# GPS.net
KiCad netlist of a schematic drawn in Altium Designer
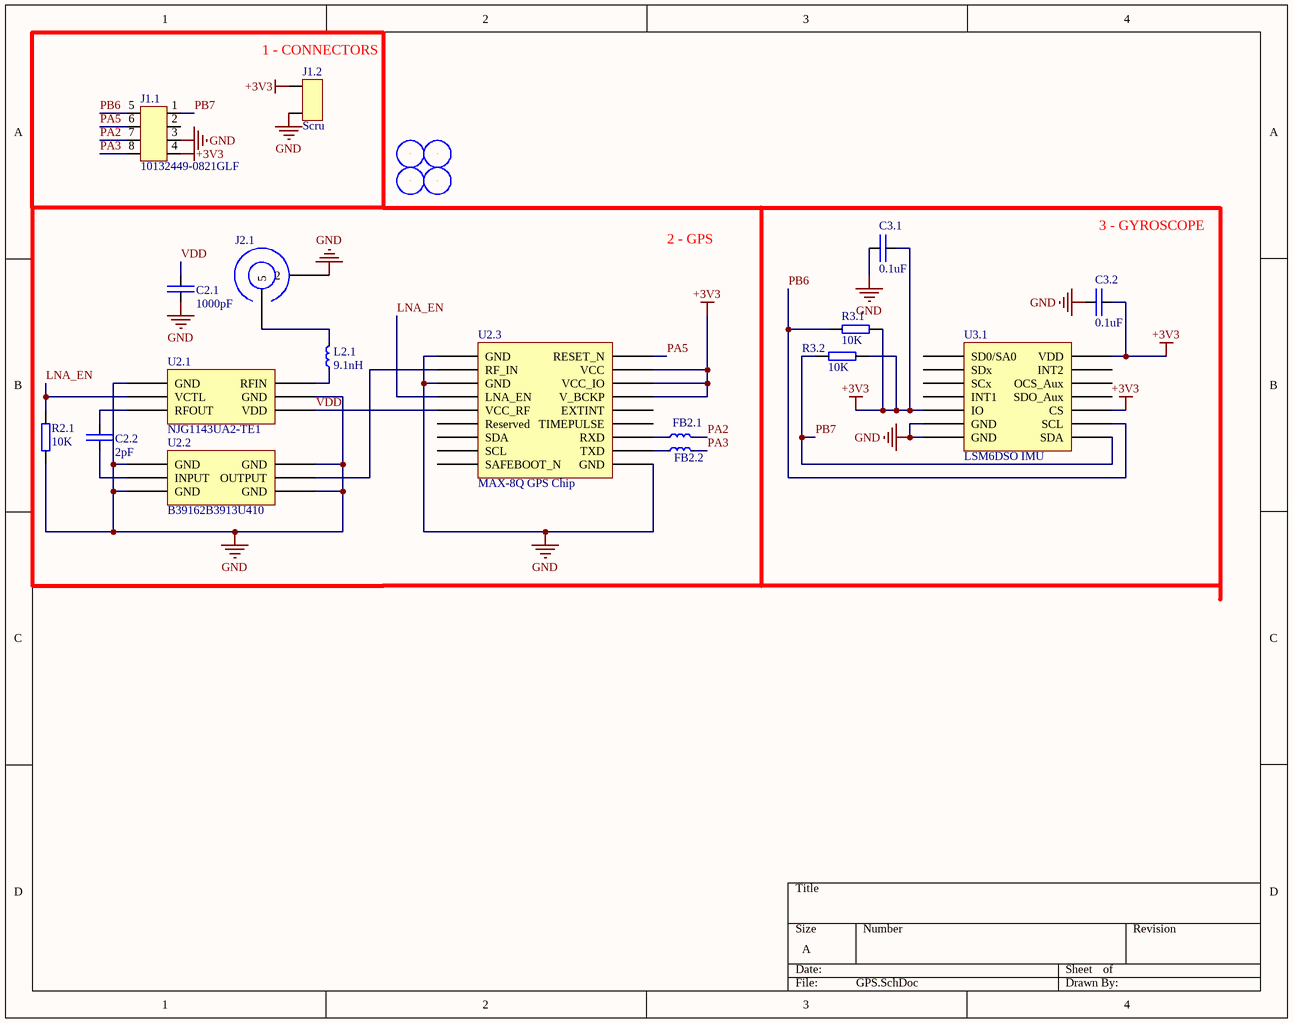
[diagram p0: GPS.SchDoc]

(export (version "E")
  (design (tool "Eeschema 10.0.6"))
  (components
    (comp (ref "C2.1")
      (value "1000pF")
      (footprint "0805")
      (description "1000pF ±5% 25V Ceramic Capacitor C0G, NP0 0805 (2012 Metric)")
      (libsource (lib "GPS_SchLib") (part "885012007040"))
    )
    (comp (ref "C2.2")
      (value "2pF")
      (footprint "0805")
      (description "2pF ±0.25pF 50V Ceramic Capacitor C0G, NP0 0805 (2012 Metric)")
      (libsource (lib "GPS_SchLib") (part "08055A2R0CAT2A"))
    )
    (comp (ref "C3.1")
      (value "0.1uF")
      (footprint "C0805")
      (description "CAP CER 0.1UF 50V X7R 0805")
      (fields
        (field (name "MANUFACTURER") "Samsung")
        (field (name "MANUFACTURER PART NUMBER") "CL21B104KBCWPNC")
      )
      (libsource (lib "Capacitors") (part "CL21B104KBCWPNC"))
    )
    (comp (ref "C3.2")
      (value "0.1uF")
      (footprint "C0805")
      (description "CAP CER 0.1UF 50V X7R 0805")
      (fields
        (field (name "MANUFACTURER") "Samsung")
        (field (name "MANUFACTURER PART NUMBER") "CL21B104KBCWPNC")
      )
      (libsource (lib "Capacitors") (part "CL21B104KBCWPNC"))
    )
    (comp (ref "FB2.1")
      (value "BLM15HD102SN1D")
      (footprint "L0402")
      (description "Ferrite Beads 0402 1Kohms Tape GHz Hi Spd Sig Line")
      (fields
        (field (name "MANUFACTURER") "Taiyo Yuden")
        (field (name "MANUFACTURER PART NUMBER") "NR6028T330M")
      )
      (libsource (lib "GPS_SchLib") (part "BLM15HD102SN1D"))
    )
    (comp (ref "FB2.2")
      (value "BLM15HD102SN1D")
      (footprint "L0402")
      (description "Ferrite Beads 0402 1Kohms Tape GHz Hi Spd Sig Line")
      (fields
        (field (name "MANUFACTURER") "Taiyo Yuden")
        (field (name "MANUFACTURER PART NUMBER") "NR6028T330M")
      )
      (libsource (lib "GPS_SchLib") (part "BLM15HD102SN1D"))
    )
    (comp (ref "J1.1")
      (value "10132449-0821GLF")
      (footprint "Micro-Fit 3.0 8pos")
      (description "Micro-fit 3.0 8pos right-angle")
      (fields (field (name "MANUFACTURER") "Molex") (field (name "MANUFACTURER PART NUMBER") "43045-0800"))
      (libsource (lib "Connectors") (part "10132449-0821GLF"))
    )
    (comp (ref "J1.2")
      (value "Scru")
      (footprint "5mm 2POS Screw terminal")
      (libsource (lib "Connectors") (part "5mm 2POS Screw terminal"))
    )
    (comp (ref "J2.1")
      (value "132136")
      (footprint "132136")
      (description "Connector, rf coaxial,SMA right angle jack for p.c. board, 4 legs, .050 cont, 50 ohm")
      (libsource (lib "GPS_SchLib") (part "132136"))
    )
    (comp (ref "L2.1")
      (value "9.1nH")
      (footprint "0402")
      (description "Fixed Inductors 9.1nH 0402")
      (libsource (lib "GPS_SchLib") (part "LQP15MN9N1B02D"))
    )
    (comp (ref "R2.1")
      (value "10K")
      (footprint "R0805")
      (description "RES SMD 10K OHM 1% 1/8W 0805")
      (fields (field (name "MANUFACTURER") "Yageo") (field (name "MANUFACTURER PART NUMBER") "ERJ-6ENF1002V"))
      (libsource (lib "Resistors") (part "ERJ6ENF1002V"))
    )
    (comp (ref "R3.1")
      (value "10K")
      (footprint "R0805")
      (description "RES SMD 10K OHM 1% 1/8W 0805")
      (fields (field (name "MANUFACTURER") "Yageo") (field (name "MANUFACTURER PART NUMBER") "ERJ-6ENF1002V"))
      (libsource (lib "Resistors") (part "ERJ6ENF1002V"))
    )
    (comp (ref "R3.2")
      (value "10K")
      (footprint "R0805")
      (description "RES SMD 10K OHM 1% 1/8W 0805")
      (fields (field (name "MANUFACTURER") "Yageo") (field (name "MANUFACTURER PART NUMBER") "ERJ-6ENF1002V"))
      (libsource (lib "Resistors") (part "ERJ6ENF1002V"))
    )
    (comp (ref "U2.1")
      (value "NJG1143UA2-TE1")
      (footprint "EPFFP6-A2")
      (description "RF Amplifier Low Noise Amp GaAs MMIC 1.5V to 3.6V")
      (libsource (lib "GPS_SchLib") (part "NJG1143UA2-TE1"))
    )
    (comp (ref "U2.2")
      (value "B39162B3913U410")
      (footprint "DCC6C")
      (description "SAW Filter 1588MHzFrequency 50Ohm SMD 6Pin")
      (libsource (lib "GPS_SchLib") (part "B39162B3913U410"))
    )
    (comp (ref "U2.3")
      (value "MAX-8Q GPS Chip")
      (footprint "MAX-8Q GPS")
      (description "High sensitivity of –166 dBm for single GNSS reception")
      (libsource (lib "GPS_SchLib") (part "MAX-8Q GPS Chip"))
    )
    (comp (ref "U3.1")
      (value "LSM6DSO IMU")
      (footprint "LSM6DSO IMU")
      (description "3D digital accelerometer and a 3D digital gyroscope")
      (libsource (lib "GPS_SchLib") (part "LSM6DSO IMU"))
    )
  )
  (nets
    (net (code "1") (name "+3V3") (class "Default")
      (node (ref "C3.1") (pin "2") (pinfunction "2_2") (pintype "passive"))
      (node (ref "C3.2") (pin "2") (pinfunction "2_2") (pintype "passive"))
      (node (ref "J1.1") (pin "4") (pinfunction "4_4") (pintype "passive"))
      (node (ref "J1.2") (pin "1") (pinfunction "1_1") (pintype "passive"))
      (node (ref "R3.1") (pin "2") (pinfunction "2_2") (pintype "passive"))
      (node (ref "R3.2") (pin "2") (pinfunction "2_2") (pintype "passive"))
      (node (ref "U2.3") (pin "6") (pinfunction "V_BCKP_6") (pintype "passive"))
      (node (ref "U2.3") (pin "7") (pinfunction "VCC_IO_7") (pintype "passive"))
      (node (ref "U2.3") (pin "8") (pinfunction "VCC_8") (pintype "passive"))
      (node (ref "U3.1") (pin "12") (pinfunction "CS_12") (pintype "passive"))
      (node (ref "U3.1") (pin "5") (pinfunction "IO_5") (pintype "passive"))
      (node (ref "U3.1") (pin "8") (pinfunction "VDD_8") (pintype "passive"))
    )
    (net (code "2") (name "/LNA_EN") (class "Default")
      (node (ref "R2.1") (pin "2") (pinfunction "2_2") (pintype "passive"))
      (node (ref "U2.1") (pin "2") (pinfunction "VCTL_2") (pintype "passive"))
      (node (ref "U2.3") (pin "13") (pinfunction "LNA_EN_13") (pintype "passive"))
    )
    (net (code "3") (name "/PA2") (class "Default")
      (node (ref "FB2.1") (pin "2") (pinfunction "2_2") (pintype "passive"))
      (node (ref "J1.1") (pin "7") (pinfunction "7_7") (pintype "passive"))
    )
    (net (code "4") (name "/PA3") (class "Default")
      (node (ref "FB2.2") (pin "2") (pinfunction "2_2") (pintype "passive"))
      (node (ref "J1.1") (pin "8") (pinfunction "8_8") (pintype "passive"))
    )
    (net (code "5") (name "/PA5") (class "Default")
      (node (ref "J1.1") (pin "6") (pinfunction "6_6") (pintype "passive"))
      (node (ref "U2.3") (pin "9") (pinfunction "RESET_N_9") (pintype "passive"))
    )
    (net (code "6") (name "/PB6") (class "Default")
      (node (ref "J1.1") (pin "5") (pinfunction "5_5") (pintype "passive"))
      (node (ref "R3.1") (pin "1") (pinfunction "1_1") (pintype "passive"))
      (node (ref "U3.1") (pin "13") (pinfunction "SCL_13") (pintype "passive"))
    )
    (net (code "7") (name "/PB7") (class "Default")
      (node (ref "J1.1") (pin "1") (pinfunction "1_1") (pintype "passive"))
      (node (ref "R3.2") (pin "1") (pinfunction "1_1") (pintype "passive"))
      (node (ref "U3.1") (pin "14") (pinfunction "SDA_14") (pintype "passive"))
    )
    (net (code "8") (name "/VDD") (class "Default")
      (node (ref "C2.1") (pin "2") (pinfunction "2_2") (pintype "passive"))
      (node (ref "U2.1") (pin "4") (pinfunction "VDD_4") (pintype "passive"))
      (node (ref "U2.3") (pin "14") (pinfunction "VCC_RF_14") (pintype "passive"))
    )
    (net (code "9") (name "GND") (class "Default")
      (node (ref "C2.1") (pin "1") (pinfunction "1_1") (pintype "passive"))
      (node (ref "C3.1") (pin "1") (pinfunction "1_1") (pintype "passive"))
      (node (ref "C3.2") (pin "1") (pinfunction "1_1") (pintype "passive"))
      (node (ref "J1.1") (pin "3") (pinfunction "3_3") (pintype "passive"))
      (node (ref "J1.2") (pin "2") (pinfunction "2_2") (pintype "passive"))
      (node (ref "J2.1") (pin "2") (pinfunction "2_2") (pintype "passive"))
      (node (ref "R2.1") (pin "1") (pinfunction "1_1") (pintype "passive"))
      (node (ref "U2.1") (pin "1") (pinfunction "GND_1") (pintype "passive"))
      (node (ref "U2.1") (pin "5") (pinfunction "GND_5") (pintype "passive"))
      (node (ref "U2.2") (pin "1") (pinfunction "GND_1") (pintype "passive"))
      (node (ref "U2.2") (pin "3") (pinfunction "GND_3") (pintype "passive"))
      (node (ref "U2.2") (pin "4") (pinfunction "GND_4") (pintype "passive"))
      (node (ref "U2.2") (pin "6") (pinfunction "GND_6") (pintype "passive"))
      (node (ref "U2.3") (pin "1") (pinfunction "GND_1") (pintype "passive"))
      (node (ref "U2.3") (pin "10") (pinfunction "GND_10") (pintype "passive"))
      (node (ref "U2.3") (pin "12") (pinfunction "GND_12") (pintype "passive"))
      (node (ref "U3.1") (pin "6") (pinfunction "GND_6") (pintype "passive"))
      (node (ref "U3.1") (pin "7") (pinfunction "GND_7") (pintype "passive"))
    )
    (net (code "10") (name "Net-(J2.1-Pad5)") (class "Default")
      (node (ref "J2.1") (pin "5") (pinfunction "5_5") (pintype "passive"))
      (node (ref "L2.1") (pin "2") (pinfunction "2_2") (pintype "passive"))
    )
    (net (code "11") (name "Net-(U2.1-RFIN)") (class "Default")
      (node (ref "L2.1") (pin "1") (pinfunction "1_1") (pintype "passive"))
      (node (ref "U2.1") (pin "6") (pinfunction "RFIN_6") (pintype "passive"))
    )
    (net (code "12") (name "Net-(U2.1-RFOUT)") (class "Default")
      (node (ref "C2.2") (pin "2") (pinfunction "2_2") (pintype "passive"))
      (node (ref "U2.1") (pin "3") (pinfunction "RFOUT_3") (pintype "passive"))
    )
    (net (code "13") (name "Net-(U2.2-INPUT)") (class "Default")
      (node (ref "C2.2") (pin "1") (pinfunction "1_1") (pintype "passive"))
      (node (ref "U2.2") (pin "2") (pinfunction "INPUT_2") (pintype "passive"))
    )
    (net (code "14") (name "Net-(U2.2-OUTPUT)") (class "Default")
      (node (ref "U2.2") (pin "5") (pinfunction "OUTPUT_5") (pintype "passive"))
      (node (ref "U2.3") (pin "11") (pinfunction "RF_IN_11") (pintype "passive"))
    )
    (net (code "15") (name "Net-(U2.3-RXD)") (class "Default")
      (node (ref "FB2.1") (pin "1") (pinfunction "1_1") (pintype "passive"))
      (node (ref "U2.3") (pin "3") (pinfunction "RXD_3") (pintype "passive"))
    )
    (net (code "16") (name "Net-(U2.3-TXD)") (class "Default")
      (node (ref "FB2.2") (pin "1") (pinfunction "1_1") (pintype "passive"))
      (node (ref "U2.3") (pin "2") (pinfunction "TXD_2") (pintype "passive"))
    )
    (net (code "21") (name "unconnected-(J1.1-Pad2)") (class "Default")
      (node (ref "J1.1") (pin "2") (pinfunction "2_2") (pintype "passive"))
    )
    (net (code "22") (name "unconnected-(U2.3-EXTINT-Pad5)") (class "Default")
      (node (ref "U2.3") (pin "5") (pinfunction "EXTINT_5") (pintype "passive"))
    )
    (net (code "23") (name "unconnected-(U2.3-Reserved-Pad15)") (class "Default")
      (node (ref "U2.3") (pin "15") (pinfunction "Reserved_15") (pintype "passive"))
    )
    (net (code "24") (name "unconnected-(U2.3-SAFEBOOT_N-Pad18)") (class "Default")
      (node (ref "U2.3") (pin "18") (pinfunction "SAFEBOOT_N_18") (pintype "passive"))
    )
    (net (code "25") (name "unconnected-(U2.3-SCL-Pad17)") (class "Default")
      (node (ref "U2.3") (pin "17") (pinfunction "SCL_17") (pintype "passive"))
    )
    (net (code "26") (name "unconnected-(U2.3-SDA-Pad16)") (class "Default")
      (node (ref "U2.3") (pin "16") (pinfunction "SDA_16") (pintype "passive"))
    )
    (net (code "27") (name "unconnected-(U2.3-TIMEPULSE-Pad4)") (class "Default")
      (node (ref "U2.3") (pin "4") (pinfunction "TIMEPULSE_4") (pintype "passive"))
    )
    (net (code "28") (name "unconnected-(U3.1-INT1-Pad4)") (class "Default")
      (node (ref "U3.1") (pin "4") (pinfunction "INT1_4") (pintype "passive"))
    )
    (net (code "29") (name "unconnected-(U3.1-INT2-Pad9)") (class "Default")
      (node (ref "U3.1") (pin "9") (pinfunction "INT2_9") (pintype "passive"))
    )
    (net (code "30") (name "unconnected-(U3.1-OCS_Aux-Pad10)") (class "Default")
      (node (ref "U3.1") (pin "10") (pinfunction "OCS_Aux_10") (pintype "passive"))
    )
    (net (code "31") (name "unconnected-(U3.1-SCx-Pad3)") (class "Default")
      (node (ref "U3.1") (pin "3") (pinfunction "SCx_3") (pintype "passive"))
    )
    (net (code "32") (name "unconnected-(U3.1-SD0{slash}SA0-Pad1)") (class "Default")
      (node (ref "U3.1") (pin "1") (pinfunction "SD0/SA0_1") (pintype "passive"))
    )
    (net (code "33") (name "unconnected-(U3.1-SDO_Aux-Pad11)") (class "Default")
      (node (ref "U3.1") (pin "11") (pinfunction "SDO_Aux_11") (pintype "passive"))
    )
    (net (code "34") (name "unconnected-(U3.1-SDx-Pad2)") (class "Default")
      (node (ref "U3.1") (pin "2") (pinfunction "SDx_2") (pintype "passive"))
    )
  )
)
